# ESQ.net
KiCad netlist of a schematic drawn in Altium Designer
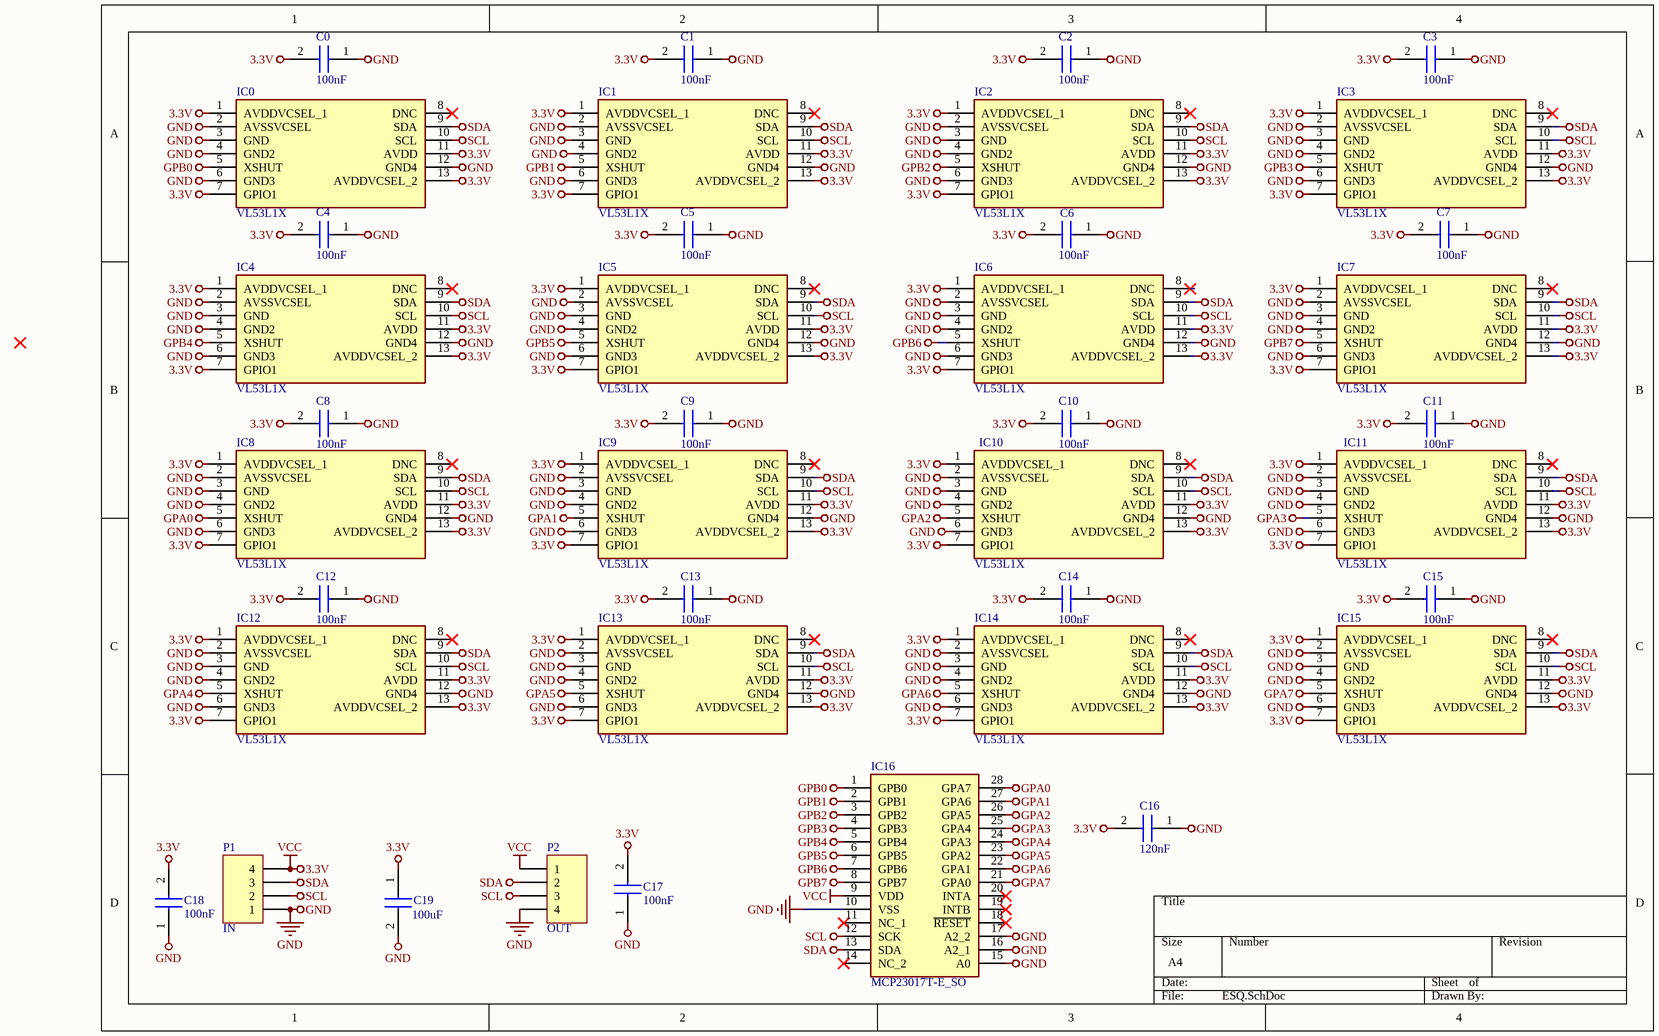
[diagram p0: ESQ.SchDoc]

(export (version "E")
  (design (tool "Eeschema 10.0.6"))
  (components
    (comp (ref "C0")
      (value "100nF")
      (footprint "SamacSys:CAPC1608X90N")
      (description "Capacitor")
      (fields
        (field (name "MANUFACTURER_PART_NUMBER") "0603YC104K4T2A")
        (field (name "MOUSER PART NUMBER") "581-0603YC104K4")
      )
      (libsource (lib "*") (part "0603YC104K4T2A"))
    )
    (comp (ref "C1")
      (value "100nF")
      (footprint "SamacSys:CAPC1608X90N")
      (description "Capacitor")
      (fields
        (field (name "MANUFACTURER_PART_NUMBER") "0603YC104K4T2A")
        (field (name "MOUSER PART NUMBER") "581-0603YC104K4")
      )
      (libsource (lib "*") (part "0603YC104K4T2A"))
    )
    (comp (ref "C2")
      (value "100nF")
      (footprint "SamacSys:CAPC1608X90N")
      (description "Capacitor")
      (fields
        (field (name "MANUFACTURER_PART_NUMBER") "0603YC104K4T2A")
        (field (name "MOUSER PART NUMBER") "581-0603YC104K4")
      )
      (libsource (lib "*") (part "0603YC104K4T2A"))
    )
    (comp (ref "C3")
      (value "100nF")
      (footprint "SamacSys:CAPC1608X90N")
      (description "Capacitor")
      (fields
        (field (name "MANUFACTURER_PART_NUMBER") "0603YC104K4T2A")
        (field (name "MOUSER PART NUMBER") "581-0603YC104K4")
      )
      (libsource (lib "*") (part "0603YC104K4T2A"))
    )
    (comp (ref "C4")
      (value "100nF")
      (footprint "SamacSys:CAPC1608X90N")
      (description "Capacitor")
      (fields
        (field (name "MANUFACTURER_PART_NUMBER") "0603YC104K4T2A")
        (field (name "MOUSER PART NUMBER") "581-0603YC104K4")
      )
      (libsource (lib "*") (part "0603YC104K4T2A"))
    )
    (comp (ref "C5")
      (value "100nF")
      (footprint "SamacSys:CAPC1608X90N")
      (description "Capacitor")
      (fields
        (field (name "MANUFACTURER_PART_NUMBER") "0603YC104K4T2A")
        (field (name "MOUSER PART NUMBER") "581-0603YC104K4")
      )
      (libsource (lib "*") (part "0603YC104K4T2A"))
    )
    (comp (ref "C6")
      (value "100nF")
      (footprint "SamacSys:CAPC1608X90N")
      (description "Capacitor")
      (fields
        (field (name "MANUFACTURER_PART_NUMBER") "0603YC104K4T2A")
        (field (name "MOUSER PART NUMBER") "581-0603YC104K4")
      )
      (libsource (lib "*") (part "0603YC104K4T2A"))
    )
    (comp (ref "C7")
      (value "100nF")
      (footprint "SamacSys:CAPC1608X90N")
      (description "Capacitor")
      (fields
        (field (name "MANUFACTURER_PART_NUMBER") "0603YC104K4T2A")
        (field (name "MOUSER PART NUMBER") "581-0603YC104K4")
      )
      (libsource (lib "*") (part "0603YC104K4T2A"))
    )
    (comp (ref "C8")
      (value "100nF")
      (footprint "SamacSys:CAPC1608X90N")
      (description "Capacitor")
      (fields
        (field (name "MANUFACTURER_PART_NUMBER") "0603YC104K4T2A")
        (field (name "MOUSER PART NUMBER") "581-0603YC104K4")
      )
      (libsource (lib "*") (part "0603YC104K4T2A"))
    )
    (comp (ref "C9")
      (value "100nF")
      (footprint "SamacSys:CAPC1608X90N")
      (description "Capacitor")
      (fields
        (field (name "MANUFACTURER_PART_NUMBER") "0603YC104K4T2A")
        (field (name "MOUSER PART NUMBER") "581-0603YC104K4")
      )
      (libsource (lib "*") (part "0603YC104K4T2A"))
    )
    (comp (ref "C10")
      (value "100nF")
      (footprint "SamacSys:CAPC1608X90N")
      (description "Capacitor")
      (fields
        (field (name "MANUFACTURER_PART_NUMBER") "0603YC104K4T2A")
        (field (name "MOUSER PART NUMBER") "581-0603YC104K4")
      )
      (libsource (lib "*") (part "0603YC104K4T2A"))
    )
    (comp (ref "C11")
      (value "100nF")
      (footprint "SamacSys:CAPC1608X90N")
      (description "Capacitor")
      (fields
        (field (name "MANUFACTURER_PART_NUMBER") "0603YC104K4T2A")
        (field (name "MOUSER PART NUMBER") "581-0603YC104K4")
      )
      (libsource (lib "*") (part "0603YC104K4T2A"))
    )
    (comp (ref "C12")
      (value "100nF")
      (footprint "SamacSys:CAPC1608X90N")
      (description "Capacitor")
      (fields
        (field (name "MANUFACTURER_PART_NUMBER") "0603YC104K4T2A")
        (field (name "MOUSER PART NUMBER") "581-0603YC104K4")
      )
      (libsource (lib "*") (part "0603YC104K4T2A"))
    )
    (comp (ref "C13")
      (value "100nF")
      (footprint "SamacSys:CAPC1608X90N")
      (description "Capacitor")
      (fields
        (field (name "MANUFACTURER_PART_NUMBER") "0603YC104K4T2A")
        (field (name "MOUSER PART NUMBER") "581-0603YC104K4")
      )
      (libsource (lib "*") (part "0603YC104K4T2A"))
    )
    (comp (ref "C14")
      (value "100nF")
      (footprint "SamacSys:CAPC1608X90N")
      (description "Capacitor")
      (fields
        (field (name "MANUFACTURER_PART_NUMBER") "0603YC104K4T2A")
        (field (name "MOUSER PART NUMBER") "581-0603YC104K4")
      )
      (libsource (lib "*") (part "0603YC104K4T2A"))
    )
    (comp (ref "C15")
      (value "100nF")
      (footprint "SamacSys:CAPC1608X90N")
      (description "Capacitor")
      (fields
        (field (name "MANUFACTURER_PART_NUMBER") "0603YC104K4T2A")
        (field (name "MOUSER PART NUMBER") "581-0603YC104K4")
      )
      (libsource (lib "*") (part "0603YC104K4T2A"))
    )
    (comp (ref "C16")
      (value "120nF")
      (footprint "SamacSys:CAPC1608X90N")
      (description "Capacitor")
      (fields
        (field (name "MANUFACTURER_PART_NUMBER") "0603YC104K4T2A")
        (field (name "MOUSER PART NUMBER") "581-0603YC104K4")
      )
      (libsource (lib "*") (part "0603YC104K4T2A"))
    )
    (comp (ref "C17")
      (value "100nF")
      (footprint "SamacSys:CAPC1608X90N")
      (description "Capacitor")
      (fields
        (field (name "MANUFACTURER_PART_NUMBER") "0603YC104K4T2A")
        (field (name "MOUSER PART NUMBER") "581-0603YC104K4")
      )
      (libsource (lib "*") (part "0603YC104K4T2A"))
    )
    (comp (ref "C18")
      (value "100nF")
      (footprint "SamacSys:CAPC1608X90N")
      (description "Capacitor")
      (fields
        (field (name "MANUFACTURER_PART_NUMBER") "0603YC104K4T2A")
        (field (name "MOUSER PART NUMBER") "581-0603YC104K4")
      )
      (libsource (lib "*") (part "0603YC104K4T2A"))
    )
    (comp (ref "C19")
      (value "100uF")
      (footprint "SamacSys:CAPC1608X90N")
      (description "Capacitor")
      (fields
        (field (name "MANUFACTURER_PART_NUMBER") "06033C474MAT2A")
        (field (name "MOUSER PART NUMBER") "581-06033C474MAT2A")
      )
      (libsource (lib "*") (part "06033C474MAT2A"))
    )
    (comp (ref "IC0")
      (value "VL53L1X")
      (footprint "SamacSys:VL53L1X")
      (description "Integrated Circuit")
      (libsource (lib "*") (part "VL53L1X"))
    )
    (comp (ref "IC1")
      (value "VL53L1X")
      (footprint "SamacSys:VL53L1X")
      (description "Integrated Circuit")
      (libsource (lib "*") (part "VL53L1X"))
    )
    (comp (ref "IC2")
      (value "VL53L1X")
      (footprint "SamacSys:VL53L1X")
      (description "Integrated Circuit")
      (libsource (lib "*") (part "VL53L1X"))
    )
    (comp (ref "IC3")
      (value "VL53L1X")
      (footprint "SamacSys:VL53L1X")
      (description "Integrated Circuit")
      (libsource (lib "*") (part "VL53L1X"))
    )
    (comp (ref "IC4")
      (value "VL53L1X")
      (footprint "SamacSys:VL53L1X")
      (description "Integrated Circuit")
      (libsource (lib "*") (part "VL53L1X"))
    )
    (comp (ref "IC5")
      (value "VL53L1X")
      (footprint "SamacSys:VL53L1X")
      (description "Integrated Circuit")
      (libsource (lib "*") (part "VL53L1X"))
    )
    (comp (ref "IC6")
      (value "VL53L1X")
      (footprint "SamacSys:VL53L1X")
      (description "Integrated Circuit")
      (libsource (lib "*") (part "VL53L1X"))
    )
    (comp (ref "IC7")
      (value "VL53L1X")
      (footprint "SamacSys:VL53L1X")
      (description "Integrated Circuit")
      (libsource (lib "*") (part "VL53L1X"))
    )
    (comp (ref "IC8")
      (value "VL53L1X")
      (footprint "SamacSys:VL53L1X")
      (description "Integrated Circuit")
      (libsource (lib "*") (part "VL53L1X"))
    )
    (comp (ref "IC9")
      (value "VL53L1X")
      (footprint "SamacSys:VL53L1X")
      (description "Integrated Circuit")
      (libsource (lib "*") (part "VL53L1X"))
    )
    (comp (ref "IC10")
      (value "VL53L1X")
      (footprint "SamacSys:VL53L1X")
      (description "Integrated Circuit")
      (libsource (lib "*") (part "VL53L1X"))
    )
    (comp (ref "IC11")
      (value "VL53L1X")
      (footprint "SamacSys:VL53L1X")
      (description "Integrated Circuit")
      (libsource (lib "*") (part "VL53L1X"))
    )
    (comp (ref "IC12")
      (value "VL53L1X")
      (footprint "SamacSys:VL53L1X")
      (description "Integrated Circuit")
      (libsource (lib "*") (part "VL53L1X"))
    )
    (comp (ref "IC13")
      (value "VL53L1X")
      (footprint "SamacSys:VL53L1X")
      (description "Integrated Circuit")
      (libsource (lib "*") (part "VL53L1X"))
    )
    (comp (ref "IC14")
      (value "VL53L1X")
      (footprint "SamacSys:VL53L1X")
      (description "Integrated Circuit")
      (libsource (lib "*") (part "VL53L1X"))
    )
    (comp (ref "IC15")
      (value "VL53L1X")
      (footprint "SamacSys:VL53L1X")
      (description "Integrated Circuit")
      (libsource (lib "*") (part "VL53L1X"))
    )
    (comp (ref "IC16")
      (value "MCP23017T-E_SO")
      (footprint "SamacSys:SOIC127P1030X265-28N")
      (description "Integrated Circuit")
      (fields
        (field (name "MANUFACTURER_PART_NUMBER") "MCP23017T-E/SO")
        (field (name "MOUSER PART NUMBER") "579-MCP23017T-E/SO")
      )
      (libsource (lib "*") (part "MCP23017T-E_SO"))
    )
    (comp (ref "P1")
      (value "IN")
      (footprint "HDR1X4")
      (description "Header, 4-Pin")
      (fields (field (name "PUBLISHER") "Altium Limited"))
      (libsource (lib "") (part "Header 4_1"))
    )
    (comp (ref "P2")
      (value "OUT")
      (footprint "HDR1X4")
      (description "Header, 4-Pin")
      (fields (field (name "PUBLISHER") "Altium Limited"))
      (libsource (lib "Miscellaneous Connectors") (part "Header 4"))
    )
  )
  (nets
    (net (code "1") (name "3.3V") (class "Default")
      (node (ref "C0") (pin "2") (pinfunction "2_2") (pintype "passive"))
      (node (ref "C1") (pin "2") (pinfunction "2_2") (pintype "passive"))
      (node (ref "C10") (pin "2") (pinfunction "2_2") (pintype "passive"))
      (node (ref "C11") (pin "2") (pinfunction "2_2") (pintype "passive"))
      (node (ref "C12") (pin "2") (pinfunction "2_2") (pintype "passive"))
      (node (ref "C13") (pin "2") (pinfunction "2_2") (pintype "passive"))
      (node (ref "C14") (pin "2") (pinfunction "2_2") (pintype "passive"))
      (node (ref "C15") (pin "2") (pinfunction "2_2") (pintype "passive"))
      (node (ref "C16") (pin "2") (pinfunction "2_2") (pintype "passive"))
      (node (ref "C17") (pin "2") (pinfunction "2_2") (pintype "passive"))
      (node (ref "C18") (pin "2") (pinfunction "2_2") (pintype "passive"))
      (node (ref "C19") (pin "1") (pinfunction "1_1") (pintype "passive"))
      (node (ref "C2") (pin "2") (pinfunction "2_2") (pintype "passive"))
      (node (ref "C3") (pin "2") (pinfunction "2_2") (pintype "passive"))
      (node (ref "C4") (pin "2") (pinfunction "2_2") (pintype "passive"))
      (node (ref "C5") (pin "2") (pinfunction "2_2") (pintype "passive"))
      (node (ref "C6") (pin "2") (pinfunction "2_2") (pintype "passive"))
      (node (ref "C7") (pin "2") (pinfunction "2_2") (pintype "passive"))
      (node (ref "C8") (pin "2") (pinfunction "2_2") (pintype "passive"))
      (node (ref "C9") (pin "2") (pinfunction "2_2") (pintype "passive"))
      (node (ref "IC0") (pin "1") (pinfunction "AVDDVCSEL_1_1") (pintype "passive"))
      (node (ref "IC0") (pin "11") (pinfunction "AVDD_11") (pintype "passive"))
      (node (ref "IC0") (pin "13") (pinfunction "AVDDVCSEL_2_13") (pintype "passive"))
      (node (ref "IC0") (pin "7") (pinfunction "GPIO1_7") (pintype "passive"))
      (node (ref "IC1") (pin "1") (pinfunction "AVDDVCSEL_1_1") (pintype "passive"))
      (node (ref "IC1") (pin "11") (pinfunction "AVDD_11") (pintype "passive"))
      (node (ref "IC1") (pin "13") (pinfunction "AVDDVCSEL_2_13") (pintype "passive"))
      (node (ref "IC1") (pin "7") (pinfunction "GPIO1_7") (pintype "passive"))
      (node (ref "IC10") (pin "1") (pinfunction "AVDDVCSEL_1_1") (pintype "passive"))
      (node (ref "IC10") (pin "11") (pinfunction "AVDD_11") (pintype "passive"))
      (node (ref "IC10") (pin "13") (pinfunction "AVDDVCSEL_2_13") (pintype "passive"))
      (node (ref "IC10") (pin "7") (pinfunction "GPIO1_7") (pintype "passive"))
      (node (ref "IC11") (pin "1") (pinfunction "AVDDVCSEL_1_1") (pintype "passive"))
      (node (ref "IC11") (pin "11") (pinfunction "AVDD_11") (pintype "passive"))
      (node (ref "IC11") (pin "13") (pinfunction "AVDDVCSEL_2_13") (pintype "passive"))
      (node (ref "IC11") (pin "7") (pinfunction "GPIO1_7") (pintype "passive"))
      (node (ref "IC12") (pin "1") (pinfunction "AVDDVCSEL_1_1") (pintype "passive"))
      (node (ref "IC12") (pin "11") (pinfunction "AVDD_11") (pintype "passive"))
      (node (ref "IC12") (pin "13") (pinfunction "AVDDVCSEL_2_13") (pintype "passive"))
      (node (ref "IC12") (pin "7") (pinfunction "GPIO1_7") (pintype "passive"))
      (node (ref "IC13") (pin "1") (pinfunction "AVDDVCSEL_1_1") (pintype "passive"))
      (node (ref "IC13") (pin "11") (pinfunction "AVDD_11") (pintype "passive"))
      (node (ref "IC13") (pin "13") (pinfunction "AVDDVCSEL_2_13") (pintype "passive"))
      (node (ref "IC13") (pin "7") (pinfunction "GPIO1_7") (pintype "passive"))
      (node (ref "IC14") (pin "1") (pinfunction "AVDDVCSEL_1_1") (pintype "passive"))
      (node (ref "IC14") (pin "11") (pinfunction "AVDD_11") (pintype "passive"))
      (node (ref "IC14") (pin "13") (pinfunction "AVDDVCSEL_2_13") (pintype "passive"))
      (node (ref "IC14") (pin "7") (pinfunction "GPIO1_7") (pintype "passive"))
      (node (ref "IC15") (pin "1") (pinfunction "AVDDVCSEL_1_1") (pintype "passive"))
      (node (ref "IC15") (pin "11") (pinfunction "AVDD_11") (pintype "passive"))
      (node (ref "IC15") (pin "13") (pinfunction "AVDDVCSEL_2_13") (pintype "passive"))
      (node (ref "IC15") (pin "7") (pinfunction "GPIO1_7") (pintype "passive"))
      (node (ref "IC16") (pin "9") (pinfunction "VDD_9") (pintype "passive"))
      (node (ref "IC2") (pin "1") (pinfunction "AVDDVCSEL_1_1") (pintype "passive"))
      (node (ref "IC2") (pin "11") (pinfunction "AVDD_11") (pintype "passive"))
      (node (ref "IC2") (pin "13") (pinfunction "AVDDVCSEL_2_13") (pintype "passive"))
      (node (ref "IC2") (pin "7") (pinfunction "GPIO1_7") (pintype "passive"))
      (node (ref "IC3") (pin "1") (pinfunction "AVDDVCSEL_1_1") (pintype "passive"))
      (node (ref "IC3") (pin "11") (pinfunction "AVDD_11") (pintype "passive"))
      (node (ref "IC3") (pin "13") (pinfunction "AVDDVCSEL_2_13") (pintype "passive"))
      (node (ref "IC3") (pin "7") (pinfunction "GPIO1_7") (pintype "passive"))
      (node (ref "IC4") (pin "1") (pinfunction "AVDDVCSEL_1_1") (pintype "passive"))
      (node (ref "IC4") (pin "11") (pinfunction "AVDD_11") (pintype "passive"))
      (node (ref "IC4") (pin "13") (pinfunction "AVDDVCSEL_2_13") (pintype "passive"))
      (node (ref "IC4") (pin "7") (pinfunction "GPIO1_7") (pintype "passive"))
      (node (ref "IC5") (pin "1") (pinfunction "AVDDVCSEL_1_1") (pintype "passive"))
      (node (ref "IC5") (pin "11") (pinfunction "AVDD_11") (pintype "passive"))
      (node (ref "IC5") (pin "13") (pinfunction "AVDDVCSEL_2_13") (pintype "passive"))
      (node (ref "IC5") (pin "7") (pinfunction "GPIO1_7") (pintype "passive"))
      (node (ref "IC6") (pin "1") (pinfunction "AVDDVCSEL_1_1") (pintype "passive"))
      (node (ref "IC6") (pin "11") (pinfunction "AVDD_11") (pintype "passive"))
      (node (ref "IC6") (pin "13") (pinfunction "AVDDVCSEL_2_13") (pintype "passive"))
      (node (ref "IC6") (pin "7") (pinfunction "GPIO1_7") (pintype "passive"))
      (node (ref "IC7") (pin "1") (pinfunction "AVDDVCSEL_1_1") (pintype "passive"))
      (node (ref "IC7") (pin "11") (pinfunction "AVDD_11") (pintype "passive"))
      (node (ref "IC7") (pin "13") (pinfunction "AVDDVCSEL_2_13") (pintype "passive"))
      (node (ref "IC7") (pin "7") (pinfunction "GPIO1_7") (pintype "passive"))
      (node (ref "IC8") (pin "1") (pinfunction "AVDDVCSEL_1_1") (pintype "passive"))
      (node (ref "IC8") (pin "11") (pinfunction "AVDD_11") (pintype "passive"))
      (node (ref "IC8") (pin "13") (pinfunction "AVDDVCSEL_2_13") (pintype "passive"))
      (node (ref "IC8") (pin "7") (pinfunction "GPIO1_7") (pintype "passive"))
      (node (ref "IC9") (pin "1") (pinfunction "AVDDVCSEL_1_1") (pintype "passive"))
      (node (ref "IC9") (pin "11") (pinfunction "AVDD_11") (pintype "passive"))
      (node (ref "IC9") (pin "13") (pinfunction "AVDDVCSEL_2_13") (pintype "passive"))
      (node (ref "IC9") (pin "7") (pinfunction "GPIO1_7") (pintype "passive"))
      (node (ref "P1") (pin "4") (pinfunction "4_4") (pintype "passive"))
      (node (ref "P2") (pin "1") (pinfunction "1_1") (pintype "passive"))
    )
    (net (code "2") (name "GND") (class "Default")
      (node (ref "C0") (pin "1") (pinfunction "1_1") (pintype "passive"))
      (node (ref "C1") (pin "1") (pinfunction "1_1") (pintype "passive"))
      (node (ref "C10") (pin "1") (pinfunction "1_1") (pintype "passive"))
      (node (ref "C11") (pin "1") (pinfunction "1_1") (pintype "passive"))
      (node (ref "C12") (pin "1") (pinfunction "1_1") (pintype "passive"))
      (node (ref "C13") (pin "1") (pinfunction "1_1") (pintype "passive"))
      (node (ref "C14") (pin "1") (pinfunction "1_1") (pintype "passive"))
      (node (ref "C15") (pin "1") (pinfunction "1_1") (pintype "passive"))
      (node (ref "C16") (pin "1") (pinfunction "1_1") (pintype "passive"))
      (node (ref "C17") (pin "1") (pinfunction "1_1") (pintype "passive"))
      (node (ref "C18") (pin "1") (pinfunction "1_1") (pintype "passive"))
      (node (ref "C19") (pin "2") (pinfunction "2_2") (pintype "passive"))
      (node (ref "C2") (pin "1") (pinfunction "1_1") (pintype "passive"))
      (node (ref "C3") (pin "1") (pinfunction "1_1") (pintype "passive"))
      (node (ref "C4") (pin "1") (pinfunction "1_1") (pintype "passive"))
      (node (ref "C5") (pin "1") (pinfunction "1_1") (pintype "passive"))
      (node (ref "C6") (pin "1") (pinfunction "1_1") (pintype "passive"))
      (node (ref "C7") (pin "1") (pinfunction "1_1") (pintype "passive"))
      (node (ref "C8") (pin "1") (pinfunction "1_1") (pintype "passive"))
      (node (ref "C9") (pin "1") (pinfunction "1_1") (pintype "passive"))
      (node (ref "IC0") (pin "12") (pinfunction "GND4_12") (pintype "passive"))
      (node (ref "IC0") (pin "2") (pinfunction "AVSSVCSEL_2") (pintype "passive"))
      (node (ref "IC0") (pin "3") (pinfunction "GND_3") (pintype "passive"))
      (node (ref "IC0") (pin "4") (pinfunction "GND2_4") (pintype "passive"))
      (node (ref "IC0") (pin "6") (pinfunction "GND3_6") (pintype "passive"))
      (node (ref "IC1") (pin "12") (pinfunction "GND4_12") (pintype "passive"))
      (node (ref "IC1") (pin "2") (pinfunction "AVSSVCSEL_2") (pintype "passive"))
      (node (ref "IC1") (pin "3") (pinfunction "GND_3") (pintype "passive"))
      (node (ref "IC1") (pin "6") (pinfunction "GND3_6") (pintype "passive"))
      (node (ref "IC10") (pin "12") (pinfunction "GND4_12") (pintype "passive"))
      (node (ref "IC10") (pin "2") (pinfunction "AVSSVCSEL_2") (pintype "passive"))
      (node (ref "IC10") (pin "3") (pinfunction "GND_3") (pintype "passive"))
      (node (ref "IC10") (pin "4") (pinfunction "GND2_4") (pintype "passive"))
      (node (ref "IC11") (pin "12") (pinfunction "GND4_12") (pintype "passive"))
      (node (ref "IC11") (pin "2") (pinfunction "AVSSVCSEL_2") (pintype "passive"))
      (node (ref "IC11") (pin "3") (pinfunction "GND_3") (pintype "passive"))
      (node (ref "IC11") (pin "4") (pinfunction "GND2_4") (pintype "passive"))
      (node (ref "IC11") (pin "6") (pinfunction "GND3_6") (pintype "passive"))
      (node (ref "IC12") (pin "12") (pinfunction "GND4_12") (pintype "passive"))
      (node (ref "IC12") (pin "2") (pinfunction "AVSSVCSEL_2") (pintype "passive"))
      (node (ref "IC12") (pin "3") (pinfunction "GND_3") (pintype "passive"))
      (node (ref "IC12") (pin "4") (pinfunction "GND2_4") (pintype "passive"))
      (node (ref "IC12") (pin "6") (pinfunction "GND3_6") (pintype "passive"))
      (node (ref "IC13") (pin "12") (pinfunction "GND4_12") (pintype "passive"))
      (node (ref "IC13") (pin "2") (pinfunction "AVSSVCSEL_2") (pintype "passive"))
      (node (ref "IC13") (pin "3") (pinfunction "GND_3") (pintype "passive"))
      (node (ref "IC13") (pin "4") (pinfunction "GND2_4") (pintype "passive"))
      (node (ref "IC13") (pin "6") (pinfunction "GND3_6") (pintype "passive"))
      (node (ref "IC14") (pin "12") (pinfunction "GND4_12") (pintype "passive"))
      (node (ref "IC14") (pin "2") (pinfunction "AVSSVCSEL_2") (pintype "passive"))
      (node (ref "IC14") (pin "3") (pinfunction "GND_3") (pintype "passive"))
      (node (ref "IC14") (pin "4") (pinfunction "GND2_4") (pintype "passive"))
      (node (ref "IC14") (pin "6") (pinfunction "GND3_6") (pintype "passive"))
      (node (ref "IC15") (pin "12") (pinfunction "GND4_12") (pintype "passive"))
      (node (ref "IC15") (pin "2") (pinfunction "AVSSVCSEL_2") (pintype "passive"))
      (node (ref "IC15") (pin "3") (pinfunction "GND_3") (pintype "passive"))
      (node (ref "IC15") (pin "4") (pinfunction "GND2_4") (pintype "passive"))
      (node (ref "IC15") (pin "6") (pinfunction "GND3_6") (pintype "passive"))
      (node (ref "IC16") (pin "10") (pinfunction "VSS_10") (pintype "passive"))
      (node (ref "IC16") (pin "15") (pinfunction "A0_15") (pintype "passive"))
      (node (ref "IC16") (pin "16") (pinfunction "A2_1_16") (pintype "passive"))
      (node (ref "IC16") (pin "17") (pinfunction "A2_2_17") (pintype "passive"))
      (node (ref "IC2") (pin "12") (pinfunction "GND4_12") (pintype "passive"))
      (node (ref "IC2") (pin "2") (pinfunction "AVSSVCSEL_2") (pintype "passive"))
      (node (ref "IC2") (pin "3") (pinfunction "GND_3") (pintype "passive"))
      (node (ref "IC2") (pin "4") (pinfunction "GND2_4") (pintype "passive"))
      (node (ref "IC2") (pin "6") (pinfunction "GND3_6") (pintype "passive"))
      (node (ref "IC3") (pin "12") (pinfunction "GND4_12") (pintype "passive"))
      (node (ref "IC3") (pin "2") (pinfunction "AVSSVCSEL_2") (pintype "passive"))
      (node (ref "IC3") (pin "3") (pinfunction "GND_3") (pintype "passive"))
      (node (ref "IC3") (pin "4") (pinfunction "GND2_4") (pintype "passive"))
      (node (ref "IC3") (pin "6") (pinfunction "GND3_6") (pintype "passive"))
      (node (ref "IC4") (pin "12") (pinfunction "GND4_12") (pintype "passive"))
      (node (ref "IC4") (pin "2") (pinfunction "AVSSVCSEL_2") (pintype "passive"))
      (node (ref "IC4") (pin "3") (pinfunction "GND_3") (pintype "passive"))
      (node (ref "IC4") (pin "4") (pinfunction "GND2_4") (pintype "passive"))
      (node (ref "IC4") (pin "6") (pinfunction "GND3_6") (pintype "passive"))
      (node (ref "IC5") (pin "12") (pinfunction "GND4_12") (pintype "passive"))
      (node (ref "IC5") (pin "3") (pinfunction "GND_3") (pintype "passive"))
      (node (ref "IC5") (pin "4") (pinfunction "GND2_4") (pintype "passive"))
      (node (ref "IC5") (pin "6") (pinfunction "GND3_6") (pintype "passive"))
      (node (ref "IC6") (pin "12") (pinfunction "GND4_12") (pintype "passive"))
      (node (ref "IC6") (pin "2") (pinfunction "AVSSVCSEL_2") (pintype "passive"))
      (node (ref "IC6") (pin "3") (pinfunction "GND_3") (pintype "passive"))
      (node (ref "IC6") (pin "4") (pinfunction "GND2_4") (pintype "passive"))
      (node (ref "IC6") (pin "6") (pinfunction "GND3_6") (pintype "passive"))
      (node (ref "IC7") (pin "12") (pinfunction "GND4_12") (pintype "passive"))
      (node (ref "IC7") (pin "2") (pinfunction "AVSSVCSEL_2") (pintype "passive"))
      (node (ref "IC7") (pin "3") (pinfunction "GND_3") (pintype "passive"))
      (node (ref "IC7") (pin "4") (pinfunction "GND2_4") (pintype "passive"))
      (node (ref "IC7") (pin "6") (pinfunction "GND3_6") (pintype "passive"))
      (node (ref "IC8") (pin "12") (pinfunction "GND4_12") (pintype "passive"))
      (node (ref "IC8") (pin "2") (pinfunction "AVSSVCSEL_2") (pintype "passive"))
      (node (ref "IC8") (pin "3") (pinfunction "GND_3") (pintype "passive"))
      (node (ref "IC8") (pin "4") (pinfunction "GND2_4") (pintype "passive"))
      (node (ref "IC8") (pin "6") (pinfunction "GND3_6") (pintype "passive"))
      (node (ref "IC9") (pin "12") (pinfunction "GND4_12") (pintype "passive"))
      (node (ref "IC9") (pin "2") (pinfunction "AVSSVCSEL_2") (pintype "passive"))
      (node (ref "IC9") (pin "3") (pinfunction "GND_3") (pintype "passive"))
      (node (ref "IC9") (pin "4") (pinfunction "GND2_4") (pintype "passive"))
      (node (ref "IC9") (pin "6") (pinfunction "GND3_6") (pintype "passive"))
      (node (ref "P1") (pin "1") (pinfunction "1_1") (pintype "passive"))
      (node (ref "P2") (pin "4") (pinfunction "4_4") (pintype "passive"))
    )
    (net (code "3") (name "GPA0") (class "Default")
      (node (ref "IC16") (pin "28") (pinfunction "GPA7_28") (pintype "passive"))
      (node (ref "IC8") (pin "5") (pinfunction "XSHUT_5") (pintype "passive"))
    )
    (net (code "4") (name "GPA1") (class "Default")
      (node (ref "IC16") (pin "27") (pinfunction "GPA6_27") (pintype "passive"))
    )
    (net (code "5") (name "GPA2") (class "Default")
      (node (ref "IC10") (pin "5") (pinfunction "XSHUT_5") (pintype "passive"))
      (node (ref "IC16") (pin "26") (pinfunction "GPA5_26") (pintype "passive"))
    )
    (net (code "6") (name "GPA3") (class "Default")
      (node (ref "IC11") (pin "5") (pinfunction "XSHUT_5") (pintype "passive"))
      (node (ref "IC16") (pin "25") (pinfunction "GPA4_25") (pintype "passive"))
    )
    (net (code "7") (name "GPA4") (class "Default")
      (node (ref "IC12") (pin "5") (pinfunction "XSHUT_5") (pintype "passive"))
      (node (ref "IC16") (pin "24") (pinfunction "GPA3_24") (pintype "passive"))
    )
    (net (code "8") (name "GPA5") (class "Default")
      (node (ref "IC13") (pin "5") (pinfunction "XSHUT_5") (pintype "passive"))
      (node (ref "IC16") (pin "23") (pinfunction "GPA2_23") (pintype "passive"))
    )
    (net (code "9") (name "GPA6") (class "Default")
      (node (ref "IC14") (pin "5") (pinfunction "XSHUT_5") (pintype "passive"))
      (node (ref "IC16") (pin "22") (pinfunction "GPA1_22") (pintype "passive"))
    )
    (net (code "10") (name "GPA7") (class "Default")
      (node (ref "IC15") (pin "5") (pinfunction "XSHUT_5") (pintype "passive"))
      (node (ref "IC16") (pin "21") (pinfunction "GPA0_21") (pintype "passive"))
    )
    (net (code "11") (name "GPB0") (class "Default")
      (node (ref "IC0") (pin "5") (pinfunction "XSHUT_5") (pintype "passive"))
      (node (ref "IC16") (pin "1") (pinfunction "GPB0_1") (pintype "passive"))
    )
    (net (code "12") (name "GPB1") (class "Default")
      (node (ref "IC1") (pin "5") (pinfunction "XSHUT_5") (pintype "passive"))
      (node (ref "IC16") (pin "2") (pinfunction "GPB1_2") (pintype "passive"))
    )
    (net (code "13") (name "GPB2") (class "Default")
      (node (ref "IC16") (pin "3") (pinfunction "GPB2_3") (pintype "passive"))
      (node (ref "IC2") (pin "5") (pinfunction "XSHUT_5") (pintype "passive"))
    )
    (net (code "14") (name "GPB3") (class "Default")
      (node (ref "IC16") (pin "4") (pinfunction "GPB3_4") (pintype "passive"))
      (node (ref "IC3") (pin "5") (pinfunction "XSHUT_5") (pintype "passive"))
    )
    (net (code "15") (name "GPB4") (class "Default")
      (node (ref "IC16") (pin "5") (pinfunction "GPB4_5") (pintype "passive"))
      (node (ref "IC4") (pin "5") (pinfunction "XSHUT_5") (pintype "passive"))
    )
    (net (code "16") (name "GPB5") (class "Default")
      (node (ref "IC16") (pin "6") (pinfunction "GPB5_6") (pintype "passive"))
      (node (ref "IC5") (pin "5") (pinfunction "XSHUT_5") (pintype "passive"))
    )
    (net (code "17") (name "GPB6") (class "Default")
      (node (ref "IC16") (pin "7") (pinfunction "GPB6_7") (pintype "passive"))
      (node (ref "IC6") (pin "5") (pinfunction "XSHUT_5") (pintype "passive"))
    )
    (net (code "18") (name "GPB7") (class "Default")
      (node (ref "IC16") (pin "8") (pinfunction "GPB7_8") (pintype "passive"))
      (node (ref "IC7") (pin "5") (pinfunction "XSHUT_5") (pintype "passive"))
    )
    (net (code "19") (name "SCL") (class "Default")
      (node (ref "IC0") (pin "10") (pinfunction "SCL_10") (pintype "passive"))
      (node (ref "IC1") (pin "10") (pinfunction "SCL_10") (pintype "passive"))
      (node (ref "IC10") (pin "10") (pinfunction "SCL_10") (pintype "passive"))
      (node (ref "IC11") (pin "10") (pinfunction "SCL_10") (pintype "passive"))
      (node (ref "IC12") (pin "10") (pinfunction "SCL_10") (pintype "passive"))
      (node (ref "IC13") (pin "10") (pinfunction "SCL_10") (pintype "passive"))
      (node (ref "IC14") (pin "10") (pinfunction "SCL_10") (pintype "passive"))
      (node (ref "IC15") (pin "10") (pinfunction "SCL_10") (pintype "passive"))
      (node (ref "IC16") (pin "12") (pinfunction "SCK_12") (pintype "passive"))
      (node (ref "IC2") (pin "10") (pinfunction "SCL_10") (pintype "passive"))
      (node (ref "IC3") (pin "10") (pinfunction "SCL_10") (pintype "passive"))
      (node (ref "IC4") (pin "10") (pinfunction "SCL_10") (pintype "passive"))
      (node (ref "IC5") (pin "10") (pinfunction "SCL_10") (pintype "passive"))
      (node (ref "IC6") (pin "10") (pinfunction "SCL_10") (pintype "passive"))
      (node (ref "IC7") (pin "10") (pinfunction "SCL_10") (pintype "passive"))
      (node (ref "IC8") (pin "10") (pinfunction "SCL_10") (pintype "passive"))
      (node (ref "IC9") (pin "10") (pinfunction "SCL_10") (pintype "passive"))
      (node (ref "P1") (pin "2") (pinfunction "2_2") (pintype "passive"))
      (node (ref "P2") (pin "3") (pinfunction "3_3") (pintype "passive"))
    )
    (net (code "20") (name "SDA") (class "Default")
      (node (ref "IC0") (pin "9") (pinfunction "SDA_9") (pintype "passive"))
      (node (ref "IC1") (pin "9") (pinfunction "SDA_9") (pintype "passive"))
      (node (ref "IC10") (pin "9") (pinfunction "SDA_9") (pintype "passive"))
      (node (ref "IC11") (pin "9") (pinfunction "SDA_9") (pintype "passive"))
      (node (ref "IC12") (pin "9") (pinfunction "SDA_9") (pintype "passive"))
      (node (ref "IC13") (pin "9") (pinfunction "SDA_9") (pintype "passive"))
      (node (ref "IC14") (pin "9") (pinfunction "SDA_9") (pintype "passive"))
      (node (ref "IC15") (pin "9") (pinfunction "SDA_9") (pintype "passive"))
      (node (ref "IC16") (pin "13") (pinfunction "SDA_13") (pintype "passive"))
      (node (ref "IC2") (pin "9") (pinfunction "SDA_9") (pintype "passive"))
      (node (ref "IC3") (pin "9") (pinfunction "SDA_9") (pintype "passive"))
      (node (ref "IC4") (pin "9") (pinfunction "SDA_9") (pintype "passive"))
      (node (ref "IC5") (pin "9") (pinfunction "SDA_9") (pintype "passive"))
      (node (ref "IC6") (pin "9") (pinfunction "SDA_9") (pintype "passive"))
      (node (ref "IC7") (pin "9") (pinfunction "SDA_9") (pintype "passive"))
      (node (ref "IC8") (pin "9") (pinfunction "SDA_9") (pintype "passive"))
      (node (ref "IC9") (pin "9") (pinfunction "SDA_9") (pintype "passive"))
      (node (ref "P1") (pin "3") (pinfunction "3_3") (pintype "passive"))
      (node (ref "P2") (pin "2") (pinfunction "2_2") (pintype "passive"))
    )
    (net (code "21") (name "unconnected-(IC0-DNC-Pad8)") (class "Default")
      (node (ref "IC0") (pin "8") (pinfunction "DNC_8") (pintype "passive+no_connect"))
    )
    (net (code "22") (name "unconnected-(IC1-DNC-Pad8)") (class "Default")
      (node (ref "IC1") (pin "8") (pinfunction "DNC_8") (pintype "passive+no_connect"))
    )
    (net (code "23") (name "unconnected-(IC1-GND2-Pad4)") (class "Default")
      (node (ref "IC1") (pin "4") (pinfunction "GND2_4") (pintype "passive"))
    )
    (net (code "24") (name "unconnected-(IC2-DNC-Pad8)") (class "Default")
      (node (ref "IC2") (pin "8") (pinfunction "DNC_8") (pintype "passive+no_connect"))
    )
    (net (code "25") (name "unconnected-(IC3-DNC-Pad8)") (class "Default")
      (node (ref "IC3") (pin "8") (pinfunction "DNC_8") (pintype "passive+no_connect"))
    )
    (net (code "26") (name "unconnected-(IC4-DNC-Pad8)") (class "Default")
      (node (ref "IC4") (pin "8") (pinfunction "DNC_8") (pintype "passive+no_connect"))
    )
    (net (code "27") (name "unconnected-(IC5-AVSSVCSEL-Pad2)") (class "Default")
      (node (ref "IC5") (pin "2") (pinfunction "AVSSVCSEL_2") (pintype "passive"))
    )
    (net (code "28") (name "unconnected-(IC5-DNC-Pad8)") (class "Default")
      (node (ref "IC5") (pin "8") (pinfunction "DNC_8") (pintype "passive+no_connect"))
    )
    (net (code "29") (name "unconnected-(IC6-DNC-Pad8)") (class "Default")
      (node (ref "IC6") (pin "8") (pinfunction "DNC_8") (pintype "passive+no_connect"))
    )
    (net (code "30") (name "unconnected-(IC7-DNC-Pad8)") (class "Default")
      (node (ref "IC7") (pin "8") (pinfunction "DNC_8") (pintype "passive+no_connect"))
    )
    (net (code "31") (name "unconnected-(IC8-DNC-Pad8)") (class "Default")
      (node (ref "IC8") (pin "8") (pinfunction "DNC_8") (pintype "passive+no_connect"))
    )
    (net (code "32") (name "unconnected-(IC9-DNC-Pad8)") (class "Default")
      (node (ref "IC9") (pin "8") (pinfunction "DNC_8") (pintype "passive+no_connect"))
    )
    (net (code "33") (name "unconnected-(IC9-XSHUT-Pad5)") (class "Default")
      (node (ref "IC9") (pin "5") (pinfunction "XSHUT_5") (pintype "passive"))
    )
    (net (code "34") (name "unconnected-(IC10-DNC-Pad8)") (class "Default")
      (node (ref "IC10") (pin "8") (pinfunction "DNC_8") (pintype "passive+no_connect"))
    )
    (net (code "35") (name "unconnected-(IC10-GND3-Pad6)") (class "Default")
      (node (ref "IC10") (pin "6") (pinfunction "GND3_6") (pintype "passive"))
    )
    (net (code "36") (name "unconnected-(IC11-DNC-Pad8)") (class "Default")
      (node (ref "IC11") (pin "8") (pinfunction "DNC_8") (pintype "passive+no_connect"))
    )
    (net (code "37") (name "unconnected-(IC12-DNC-Pad8)") (class "Default")
      (node (ref "IC12") (pin "8") (pinfunction "DNC_8") (pintype "passive+no_connect"))
    )
    (net (code "38") (name "unconnected-(IC13-DNC-Pad8)") (class "Default")
      (node (ref "IC13") (pin "8") (pinfunction "DNC_8") (pintype "passive+no_connect"))
    )
    (net (code "39") (name "unconnected-(IC14-DNC-Pad8)") (class "Default")
      (node (ref "IC14") (pin "8") (pinfunction "DNC_8") (pintype "passive+no_connect"))
    )
    (net (code "40") (name "unconnected-(IC15-DNC-Pad8)") (class "Default")
      (node (ref "IC15") (pin "8") (pinfunction "DNC_8") (pintype "passive+no_connect"))
    )
    (net (code "41") (name "unconnected-(IC16-INTA-Pad20)") (class "Default")
      (node (ref "IC16") (pin "20") (pinfunction "INTA_20") (pintype "passive+no_connect"))
    )
    (net (code "42") (name "unconnected-(IC16-INTB-Pad19)") (class "Default")
      (node (ref "IC16") (pin "19") (pinfunction "INTB_19") (pintype "passive+no_connect"))
    )
    (net (code "43") (name "unconnected-(IC16-NC_1-Pad11)") (class "Default")
      (node (ref "IC16") (pin "11") (pinfunction "NC_1_11") (pintype "passive+no_connect"))
    )
    (net (code "44") (name "unconnected-(IC16-NC_2-Pad14)") (class "Default")
      (node (ref "IC16") (pin "14") (pinfunction "NC_2_14") (pintype "passive+no_connect"))
    )
    (net (code "45") (name "unconnected-(IC16-~{RESET}-Pad18)") (class "Default")
      (node (ref "IC16") (pin "18") (pinfunction "~{RESET}_18") (pintype "passive+no_connect"))
    )
  )
)
